# Connect_Interface.net
KiCad netlist of a schematic drawn in Altium Designer
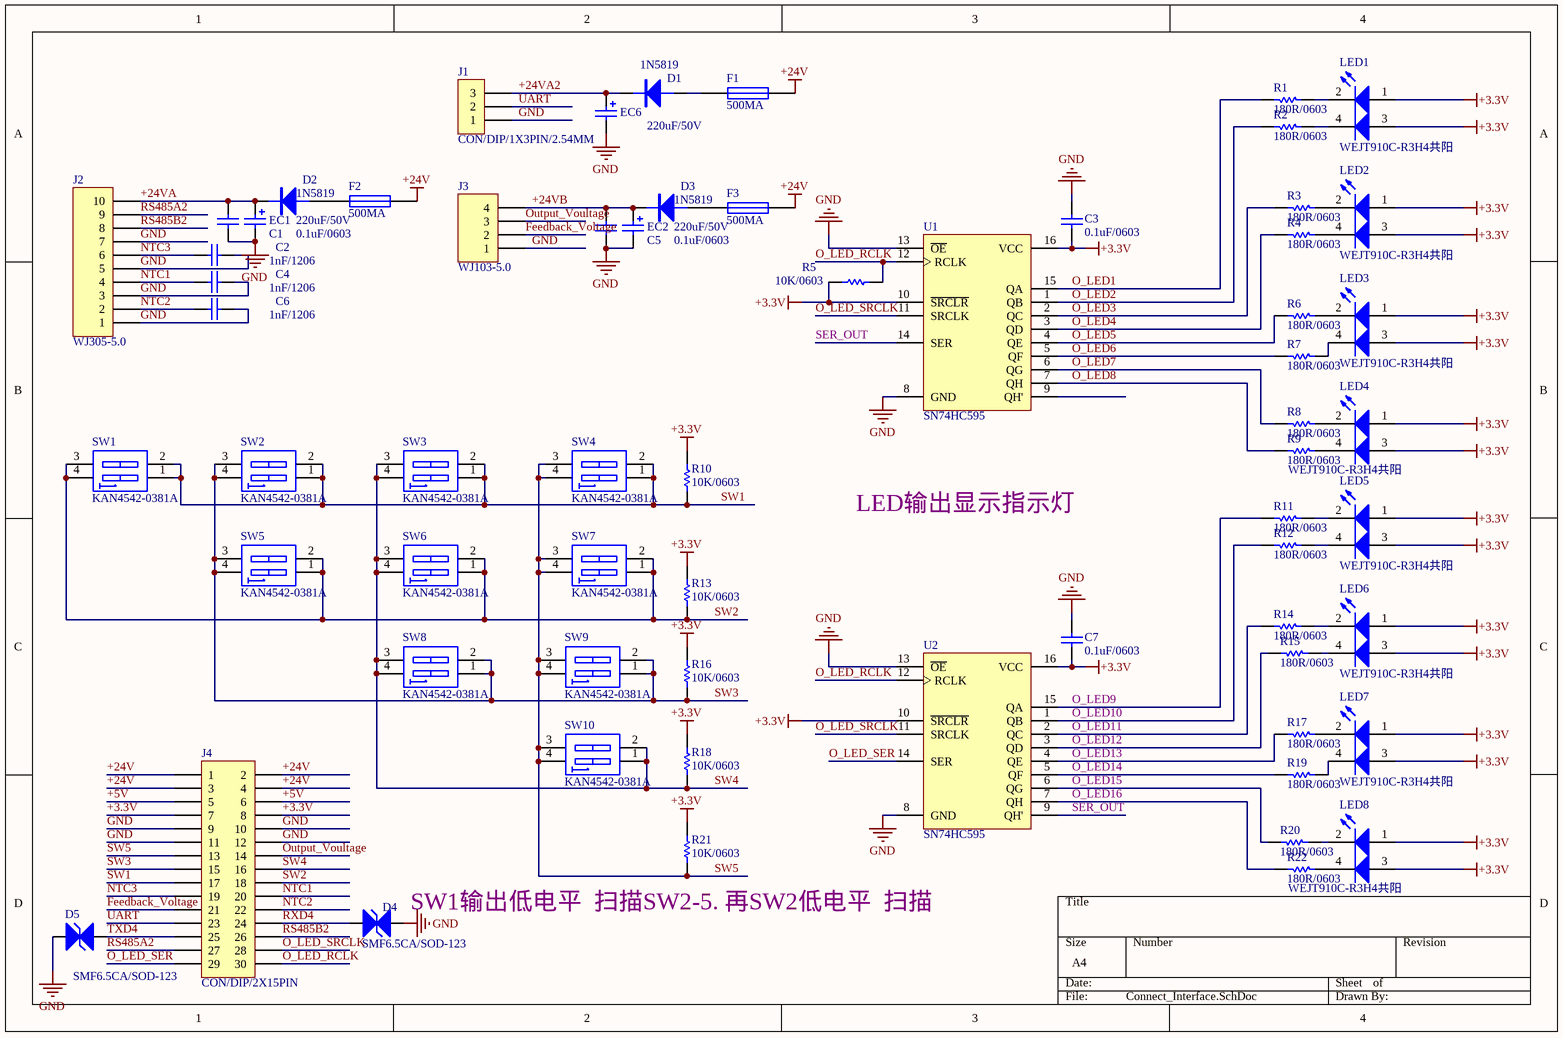
[diagram p0: Connect_Interface.SchDoc]

(export (version "E")
  (design (tool "Eeschema 10.0.6"))
  (components
    (comp (ref "C1")
      (value "0.1uF/0603")
      (footprint "CAP/SMT/0603C")
      (libsource (lib "Menred_原理图 封装库") (part "CAP/CAP/SMT/0603C"))
    )
    (comp (ref "C2")
      (value "1nF/1206")
      (footprint "CAP/SMT/1206C")
      (libsource (lib "") (part "CAP/CAP/SMT/0603C_1"))
    )
    (comp (ref "C3")
      (value "0.1uF/0603")
      (footprint "CAP/SMT/0603C")
      (libsource (lib "Menred_原理图 封装库") (part "CAP/CAP/SMT/0603C"))
    )
    (comp (ref "C4")
      (value "1nF/1206")
      (footprint "CAP/SMT/1206C")
      (libsource (lib "") (part "CAP/CAP/SMT/0603C_1"))
    )
    (comp (ref "C5")
      (value "0.1uF/0603")
      (footprint "CAP/SMT/0603C")
      (libsource (lib "Menred_原理图 封装库") (part "CAP/CAP/SMT/0603C"))
    )
    (comp (ref "C6")
      (value "1nF/1206")
      (footprint "CAP/SMT/1206C")
      (libsource (lib "") (part "CAP/CAP/SMT/0603C_1"))
    )
    (comp (ref "C7")
      (value "0.1uF/0603")
      (footprint "CAP/SMT/0603C")
      (libsource (lib "Menred_原理图 封装库") (part "CAP/CAP/SMT/0603C"))
    )
    (comp (ref "D1")
      (value "1N5819")
      (footprint "D/SMT/DO-214AC")
      (libsource (lib "Menred_原理图 封装库") (part "D/D/SMT/1N4007/DO-214"))
    )
    (comp (ref "D2")
      (value "1N5819")
      (footprint "D/SMT/DO-214AC")
      (libsource (lib "Menred_原理图 封装库") (part "D/D/SMT/1N5819/DO-214"))
    )
    (comp (ref "D3")
      (value "1N5819")
      (footprint "D/SMT/DO-214AC")
      (libsource (lib "Menred_原理图 封装库") (part "D/D/SMT/1N5819/DO-214"))
    )
    (comp (ref "D4")
      (value "SMF6.5CA/SOD-123")
      (footprint "D/SMT/SOD123")
      (libsource (lib "Menred_原理图 封装库") (part "D/TVS/SMT/SMF13CA/SOD-123"))
    )
    (comp (ref "D5")
      (value "SMF6.5CA/SOD-123")
      (footprint "D/SMT/SOD123")
      (libsource (lib "Menred_原理图 封装库") (part "D/TVS/SMT/SMF13CA/SOD-123"))
    )
    (comp (ref "EC1")
      (value "220uF/50V")
      (footprint "CAP/SMT/220UF/50V")
      (libsource (lib "Menred_原理图 封装库") (part "CAP/AEC/DIP/330uF/25V"))
    )
    (comp (ref "EC2")
      (value "220uF/50V")
      (footprint "CAP/SMT/220UF/50V")
      (libsource (lib "Menred_原理图 封装库") (part "CAP/AEC/DIP/330uF/25V"))
    )
    (comp (ref "EC6")
      (value "220uF/50V")
      (footprint "CAP/SMT/220UF/50V")
      (libsource (lib "Menred_原理图 封装库") (part "CAP/AEC/DIP/330uF/25V"))
    )
    (comp (ref "F1")
      (value "500MA")
      (footprint "FUSE/100MA/SMC")
      (libsource (lib "Menred_原理图 封装库") (part "FUSE/PTC/SMT/100MA"))
    )
    (comp (ref "F2")
      (value "500MA")
      (footprint "FUSE/100MA/SMC")
      (libsource (lib "Menred_原理图 封装库") (part "FUSE/PTC/SMT/100MA"))
    )
    (comp (ref "F3")
      (value "500MA")
      (footprint "FUSE/100MA/SMC")
      (libsource (lib "Menred_原理图 封装库") (part "FUSE/PTC/SMT/100MA"))
    )
    (comp (ref "J1")
      (value "CON/DIP/1X3PIN/2.54MM")
      (footprint "CON/DIP/1×3PIN/2.54MM/插件端子")
      (description "Connector")
      (libsource (lib "Menred_原理图 封装库") (part "CON/DIP/1X3PIN/2.54MM"))
    )
    (comp (ref "J2")
      (value "WJ305-5.0")
      (footprint "CON/DIP/1×10PIN/5.0MM/WJ103-10P")
      (description "Connector")
      (libsource (lib "Menred_原理图 封装库") (part "CON/DIP/1X10PIN/WJ305-5.0"))
    )
    (comp (ref "J3")
      (value "WJ103-5.0")
      (footprint "CON/DIP/1×4PIN/5.0MM/WJ103-4P")
      (description "Connector")
      (libsource (lib "Menred_原理图 封装库") (part "CON/DIP/1X4PIN/WJ103-5.0MM"))
    )
    (comp (ref "J4")
      (value "CON/DIP/2X15PIN")
      (footprint "CON/DIP/2X15PIN/2.54MM")
      (description "Connector")
      (fields (field (name "PUBLISHER") "Altium Limited"))
      (libsource (lib "Menred_原理图 封装库") (part "CON/DIP/2X15PIN"))
    )
    (comp (ref "LED1")
      (value "WEJT910C-R3H4共阳")
      (footprint "D/SMT/WEJT910C-R3H4")
      (libsource (lib "Menred_原理图 封装库") (part "D/LED/DIP/WEJT910C-R3H4-BA共阳"))
    )
    (comp (ref "LED2")
      (value "WEJT910C-R3H4共阳")
      (footprint "D/SMT/WEJT910C-R3H4")
      (libsource (lib "Menred_原理图 封装库") (part "D/LED/DIP/WEJT910C-R3H4-BA共阳"))
    )
    (comp (ref "LED3")
      (value "WEJT910C-R3H4共阳")
      (footprint "D/SMT/WEJT910C-R3H4")
      (libsource (lib "Menred_原理图 封装库") (part "D/LED/DIP/WEJT910C-R3H4-BA共阳"))
    )
    (comp (ref "LED4")
      (value "WEJT910C-R3H4共阳")
      (footprint "D/SMT/WEJT910C-R3H4")
      (libsource (lib "Menred_原理图 封装库") (part "D/LED/DIP/WEJT910C-R3H4-BA共阳"))
    )
    (comp (ref "LED5")
      (value "WEJT910C-R3H4共阳")
      (footprint "D/SMT/WEJT910C-R3H4")
      (libsource (lib "Menred_原理图 封装库") (part "D/LED/DIP/WEJT910C-R3H4-BA共阳"))
    )
    (comp (ref "LED6")
      (value "WEJT910C-R3H4共阳")
      (footprint "D/SMT/WEJT910C-R3H4")
      (libsource (lib "Menred_原理图 封装库") (part "D/LED/DIP/WEJT910C-R3H4-BA共阳"))
    )
    (comp (ref "LED7")
      (value "WEJT910C-R3H4共阳")
      (footprint "D/SMT/WEJT910C-R3H4")
      (libsource (lib "Menred_原理图 封装库") (part "D/LED/DIP/WEJT910C-R3H4-BA共阳"))
    )
    (comp (ref "LED8")
      (value "WEJT910C-R3H4共阳")
      (footprint "D/SMT/WEJT910C-R3H4")
      (libsource (lib "Menred_原理图 封装库") (part "D/LED/DIP/WEJT910C-R3H4-BA共阳"))
    )
    (comp (ref "R1")
      (value "180R/0603")
      (footprint "0603R")
      (libsource (lib "Menred_原理图 封装库") (part "RES/RES/SMT/0603"))
    )
    (comp (ref "R2")
      (value "180R/0603")
      (footprint "0603R")
      (libsource (lib "Menred_原理图 封装库") (part "RES/RES/SMT/0603"))
    )
    (comp (ref "R3")
      (value "180R/0603")
      (footprint "0603R")
      (libsource (lib "Menred_原理图 封装库") (part "RES/RES/SMT/0603"))
    )
    (comp (ref "R4")
      (value "180R/0603")
      (footprint "0603R")
      (libsource (lib "Menred_原理图 封装库") (part "RES/RES/SMT/0603"))
    )
    (comp (ref "R5")
      (value "10K/0603")
      (footprint "0603R")
      (libsource (lib "Menred_原理图 封装库") (part "RES/RES/SMT/0603"))
    )
    (comp (ref "R6")
      (value "180R/0603")
      (footprint "0603R")
      (libsource (lib "Menred_原理图 封装库") (part "RES/RES/SMT/0603"))
    )
    (comp (ref "R7")
      (value "180R/0603")
      (footprint "0603R")
      (libsource (lib "Menred_原理图 封装库") (part "RES/RES/SMT/0603"))
    )
    (comp (ref "R8")
      (value "180R/0603")
      (footprint "0603R")
      (libsource (lib "Menred_原理图 封装库") (part "RES/RES/SMT/0603"))
    )
    (comp (ref "R9")
      (value "180R/0603")
      (footprint "0603R")
      (libsource (lib "Menred_原理图 封装库") (part "RES/RES/SMT/0603"))
    )
    (comp (ref "R10")
      (value "10K/0603")
      (footprint "0603R")
      (libsource (lib "Menred_原理图 封装库") (part "RES/RES/SMT/0603"))
    )
    (comp (ref "R11")
      (value "180R/0603")
      (footprint "0603R")
      (libsource (lib "Menred_原理图 封装库") (part "RES/RES/SMT/0603"))
    )
    (comp (ref "R12")
      (value "180R/0603")
      (footprint "0603R")
      (libsource (lib "Menred_原理图 封装库") (part "RES/RES/SMT/0603"))
    )
    (comp (ref "R13")
      (value "10K/0603")
      (footprint "0603R")
      (libsource (lib "Menred_原理图 封装库") (part "RES/RES/SMT/0603"))
    )
    (comp (ref "R14")
      (value "180R/0603")
      (footprint "0603R")
      (libsource (lib "Menred_原理图 封装库") (part "RES/RES/SMT/0603"))
    )
    (comp (ref "R15")
      (value "180R/0603")
      (footprint "0603R")
      (libsource (lib "Menred_原理图 封装库") (part "RES/RES/SMT/0603"))
    )
    (comp (ref "R16")
      (value "10K/0603")
      (footprint "0603R")
      (libsource (lib "Menred_原理图 封装库") (part "RES/RES/SMT/0603"))
    )
    (comp (ref "R17")
      (value "180R/0603")
      (footprint "0603R")
      (libsource (lib "Menred_原理图 封装库") (part "RES/RES/SMT/0603"))
    )
    (comp (ref "R18")
      (value "10K/0603")
      (footprint "0603R")
      (libsource (lib "Menred_原理图 封装库") (part "RES/RES/SMT/0603"))
    )
    (comp (ref "R19")
      (value "180R/0603")
      (footprint "0603R")
      (libsource (lib "Menred_原理图 封装库") (part "RES/RES/SMT/0603"))
    )
    (comp (ref "R20")
      (value "180R/0603")
      (footprint "0603R")
      (libsource (lib "Menred_原理图 封装库") (part "RES/RES/SMT/0603"))
    )
    (comp (ref "R21")
      (value "10K/0603")
      (footprint "0603R")
      (libsource (lib "Menred_原理图 封装库") (part "RES/RES/SMT/0603"))
    )
    (comp (ref "R22")
      (value "180R/0603")
      (footprint "0603R")
      (libsource (lib "Menred_原理图 封装库") (part "RES/RES/SMT/0603"))
    )
    (comp (ref "SW1")
      (value "KAN4542-0381A")
      (footprint "SWITCH/KAN4542")
      (description "4.5mm*4.5mm*3.8mm")
      (libsource (lib "Menred_原理图 封装库") (part "SWITCH/TACT/SMT/KAN4542-0381A"))
    )
    (comp (ref "SW2")
      (value "KAN4542-0381A")
      (footprint "SWITCH/KAN4542")
      (description "4.5mm*4.5mm*3.8mm")
      (libsource (lib "Menred_原理图 封装库") (part "SWITCH/TACT/SMT/KAN4542-0381A"))
    )
    (comp (ref "SW3")
      (value "KAN4542-0381A")
      (footprint "SWITCH/KAN4542")
      (description "4.5mm*4.5mm*3.8mm")
      (libsource (lib "Menred_原理图 封装库") (part "SWITCH/TACT/SMT/KAN4542-0381A"))
    )
    (comp (ref "SW4")
      (value "KAN4542-0381A")
      (footprint "SWITCH/KAN4542")
      (description "4.5mm*4.5mm*3.8mm")
      (libsource (lib "Menred_原理图 封装库") (part "SWITCH/TACT/SMT/KAN4542-0381A"))
    )
    (comp (ref "SW5")
      (value "KAN4542-0381A")
      (footprint "SWITCH/KAN4542")
      (description "4.5mm*4.5mm*3.8mm")
      (libsource (lib "Menred_原理图 封装库") (part "SWITCH/TACT/SMT/KAN4542-0381A"))
    )
    (comp (ref "SW6")
      (value "KAN4542-0381A")
      (footprint "SWITCH/KAN4542")
      (description "4.5mm*4.5mm*3.8mm")
      (libsource (lib "Menred_原理图 封装库") (part "SWITCH/TACT/SMT/KAN4542-0381A"))
    )
    (comp (ref "SW7")
      (value "KAN4542-0381A")
      (footprint "SWITCH/KAN4542")
      (description "4.5mm*4.5mm*3.8mm")
      (libsource (lib "Menred_原理图 封装库") (part "SWITCH/TACT/SMT/KAN4542-0381A"))
    )
    (comp (ref "SW8")
      (value "KAN4542-0381A")
      (footprint "SWITCH/KAN4542")
      (description "4.5mm*4.5mm*3.8mm")
      (libsource (lib "Menred_原理图 封装库") (part "SWITCH/TACT/SMT/KAN4542-0381A"))
    )
    (comp (ref "SW9")
      (value "KAN4542-0381A")
      (footprint "SWITCH/KAN4542")
      (description "4.5mm*4.5mm*3.8mm")
      (libsource (lib "Menred_原理图 封装库") (part "SWITCH/TACT/SMT/KAN4542-0381A"))
    )
    (comp (ref "SW10")
      (value "KAN4542-0381A")
      (footprint "SWITCH/KAN4542")
      (description "4.5mm*4.5mm*3.8mm")
      (libsource (lib "Menred_原理图 封装库") (part "SWITCH/TACT/SMT/KAN4542-0381A"))
    )
    (comp (ref "U1")
      (value "SN74HC595")
      (footprint "SOP-16")
      (description "8-bit serial-in,serial or parallel-out shift register with output latches;3-state")
      (libsource (lib "Menred_原理图 封装库") (part "IC/TTL/SMT/SN74HC595"))
    )
    (comp (ref "U2")
      (value "SN74HC595")
      (footprint "SOP-16")
      (description "8-bit serial-in,serial or parallel-out shift register with output latches;3-state")
      (libsource (lib "Menred_原理图 封装库") (part "IC/TTL/SMT/SN74HC595"))
    )
  )
  (nets
    (net (code "1") (name "+3.3V") (class "Default")
      (node (ref "C3") (pin "1") (pinfunction "1_1") (pintype "passive"))
      (node (ref "C7") (pin "1") (pinfunction "1_1") (pintype "passive"))
      (node (ref "J4") (pin "7") (pinfunction "7_7") (pintype "passive"))
      (node (ref "J4") (pin "8") (pinfunction "8_8") (pintype "passive"))
      (node (ref "LED1") (pin "1") (pinfunction "A_1") (pintype "passive"))
      (node (ref "LED1") (pin "3") (pinfunction "A_3") (pintype "passive"))
      (node (ref "LED2") (pin "1") (pinfunction "A_1") (pintype "passive"))
      (node (ref "LED2") (pin "3") (pinfunction "A_3") (pintype "passive"))
      (node (ref "LED3") (pin "1") (pinfunction "A_1") (pintype "passive"))
      (node (ref "LED3") (pin "3") (pinfunction "A_3") (pintype "passive"))
      (node (ref "LED4") (pin "1") (pinfunction "A_1") (pintype "passive"))
      (node (ref "LED4") (pin "3") (pinfunction "A_3") (pintype "passive"))
      (node (ref "LED5") (pin "1") (pinfunction "A_1") (pintype "passive"))
      (node (ref "LED5") (pin "3") (pinfunction "A_3") (pintype "passive"))
      (node (ref "LED6") (pin "1") (pinfunction "A_1") (pintype "passive"))
      (node (ref "LED6") (pin "3") (pinfunction "A_3") (pintype "passive"))
      (node (ref "LED7") (pin "1") (pinfunction "A_1") (pintype "passive"))
      (node (ref "LED7") (pin "3") (pinfunction "A_3") (pintype "passive"))
      (node (ref "LED8") (pin "1") (pinfunction "A_1") (pintype "passive"))
      (node (ref "LED8") (pin "3") (pinfunction "A_3") (pintype "passive"))
      (node (ref "R10") (pin "2") (pinfunction "2_2") (pintype "passive"))
      (node (ref "R13") (pin "2") (pinfunction "2_2") (pintype "passive"))
      (node (ref "R16") (pin "2") (pinfunction "2_2") (pintype "passive"))
      (node (ref "R18") (pin "2") (pinfunction "2_2") (pintype "passive"))
      (node (ref "R21") (pin "2") (pinfunction "2_2") (pintype "passive"))
      (node (ref "R5") (pin "1") (pinfunction "1_1") (pintype "passive"))
      (node (ref "U1") (pin "10") (pinfunction "~{SRCLR}_10") (pintype "passive"))
      (node (ref "U1") (pin "16") (pinfunction "VCC_16") (pintype "passive"))
      (node (ref "U2") (pin "10") (pinfunction "~{SRCLR}_10") (pintype "passive"))
      (node (ref "U2") (pin "16") (pinfunction "VCC_16") (pintype "passive"))
    )
    (net (code "2") (name "+24V") (class "Default")
      (node (ref "F1") (pin "1") (pinfunction "1_1") (pintype "passive"))
      (node (ref "F2") (pin "2") (pinfunction "2_2") (pintype "passive"))
      (node (ref "F3") (pin "2") (pinfunction "2_2") (pintype "passive"))
      (node (ref "J4") (pin "1") (pinfunction "1_1") (pintype "passive"))
      (node (ref "J4") (pin "2") (pinfunction "2_2") (pintype "passive"))
      (node (ref "J4") (pin "3") (pinfunction "3_3") (pintype "passive"))
      (node (ref "J4") (pin "4") (pinfunction "4_4") (pintype "passive"))
    )
    (net (code "3") (name "/+5V") (class "Default")
      (node (ref "J4") (pin "5") (pinfunction "5_5") (pintype "passive"))
      (node (ref "J4") (pin "6") (pinfunction "6_6") (pintype "passive"))
    )
    (net (code "4") (name "/+24VA") (class "Default")
      (node (ref "C1") (pin "2") (pinfunction "2_2") (pintype "passive"))
      (node (ref "D2") (pin "1") (pinfunction "K_1") (pintype "passive"))
      (node (ref "EC1") (pin "1") (pinfunction "1_1") (pintype "passive"))
      (node (ref "J2") (pin "10") (pinfunction "10_10") (pintype "passive"))
    )
    (net (code "5") (name "/+24VA2") (class "Default")
      (node (ref "D1") (pin "1") (pinfunction "K_1") (pintype "passive"))
      (node (ref "EC6") (pin "1") (pinfunction "1_1") (pintype "passive"))
      (node (ref "J1") (pin "3") (pinfunction "3_3") (pintype "passive"))
    )
    (net (code "6") (name "/+24VB") (class "Default")
      (node (ref "C5") (pin "2") (pinfunction "2_2") (pintype "passive"))
      (node (ref "D3") (pin "1") (pinfunction "K_1") (pintype "passive"))
      (node (ref "EC2") (pin "1") (pinfunction "1_1") (pintype "passive"))
      (node (ref "J3") (pin "4") (pinfunction "4_4") (pintype "passive"))
    )
    (net (code "7") (name "/Feedback_Voltage") (class "Default")
      (node (ref "J3") (pin "2") (pinfunction "2_2") (pintype "passive"))
      (node (ref "J4") (pin "21") (pinfunction "21_21") (pintype "passive"))
    )
    (net (code "9") (name "/NTC1") (class "Default")
      (node (ref "C4") (pin "1") (pinfunction "1_1") (pintype "passive"))
      (node (ref "J2") (pin "4") (pinfunction "4_4") (pintype "passive"))
      (node (ref "J4") (pin "20") (pinfunction "20_20") (pintype "passive"))
    )
    (net (code "10") (name "/NTC2") (class "Default")
      (node (ref "C6") (pin "1") (pinfunction "1_1") (pintype "passive"))
      (node (ref "J2") (pin "2") (pinfunction "2_2") (pintype "passive"))
      (node (ref "J4") (pin "22") (pinfunction "22_22") (pintype "passive"))
    )
    (net (code "11") (name "/NTC3") (class "Default")
      (node (ref "C2") (pin "1") (pinfunction "1_1") (pintype "passive"))
      (node (ref "J2") (pin "6") (pinfunction "6_6") (pintype "passive"))
      (node (ref "J4") (pin "19") (pinfunction "19_19") (pintype "passive"))
    )
    (net (code "12") (name "/O_LED1") (class "Default")
      (node (ref "R1") (pin "1") (pinfunction "1_1") (pintype "passive"))
      (node (ref "U1") (pin "15") (pinfunction "QA_15") (pintype "passive"))
    )
    (net (code "13") (name "/O_LED2") (class "Default")
      (node (ref "R2") (pin "1") (pinfunction "1_1") (pintype "passive"))
      (node (ref "U1") (pin "1") (pinfunction "QB_1") (pintype "passive"))
    )
    (net (code "14") (name "/O_LED3") (class "Default")
      (node (ref "R3") (pin "1") (pinfunction "1_1") (pintype "passive"))
      (node (ref "U1") (pin "2") (pinfunction "QC_2") (pintype "passive"))
    )
    (net (code "15") (name "/O_LED4") (class "Default")
      (node (ref "R4") (pin "1") (pinfunction "1_1") (pintype "passive"))
      (node (ref "U1") (pin "3") (pinfunction "QD_3") (pintype "passive"))
    )
    (net (code "16") (name "/O_LED5") (class "Default")
      (node (ref "R6") (pin "1") (pinfunction "1_1") (pintype "passive"))
      (node (ref "U1") (pin "4") (pinfunction "QE_4") (pintype "passive"))
    )
    (net (code "17") (name "/O_LED6") (class "Default")
      (node (ref "R7") (pin "1") (pinfunction "1_1") (pintype "passive"))
      (node (ref "U1") (pin "5") (pinfunction "QF_5") (pintype "passive"))
    )
    (net (code "18") (name "/O_LED7") (class "Default")
      (node (ref "R8") (pin "1") (pinfunction "1_1") (pintype "passive"))
      (node (ref "U1") (pin "6") (pinfunction "QG_6") (pintype "passive"))
    )
    (net (code "19") (name "/O_LED8") (class "Default")
      (node (ref "R9") (pin "1") (pinfunction "1_1") (pintype "passive"))
      (node (ref "U1") (pin "7") (pinfunction "QH_7") (pintype "passive"))
    )
    (net (code "20") (name "/O_LED9") (class "Default")
      (node (ref "R11") (pin "1") (pinfunction "1_1") (pintype "passive"))
      (node (ref "U2") (pin "15") (pinfunction "QA_15") (pintype "passive"))
    )
    (net (code "21") (name "/O_LED10") (class "Default")
      (node (ref "R12") (pin "1") (pinfunction "1_1") (pintype "passive"))
      (node (ref "U2") (pin "1") (pinfunction "QB_1") (pintype "passive"))
    )
    (net (code "22") (name "/O_LED11") (class "Default")
      (node (ref "R14") (pin "1") (pinfunction "1_1") (pintype "passive"))
      (node (ref "U2") (pin "2") (pinfunction "QC_2") (pintype "passive"))
    )
    (net (code "23") (name "/O_LED12") (class "Default")
      (node (ref "R15") (pin "1") (pinfunction "1_1") (pintype "passive"))
      (node (ref "U2") (pin "3") (pinfunction "QD_3") (pintype "passive"))
    )
    (net (code "24") (name "/O_LED13") (class "Default")
      (node (ref "R17") (pin "1") (pinfunction "1_1") (pintype "passive"))
      (node (ref "U2") (pin "4") (pinfunction "QE_4") (pintype "passive"))
    )
    (net (code "25") (name "/O_LED14") (class "Default")
      (node (ref "R19") (pin "1") (pinfunction "1_1") (pintype "passive"))
      (node (ref "U2") (pin "5") (pinfunction "QF_5") (pintype "passive"))
    )
    (net (code "26") (name "/O_LED15") (class "Default")
      (node (ref "R20") (pin "1") (pinfunction "1_1") (pintype "passive"))
      (node (ref "U2") (pin "6") (pinfunction "QG_6") (pintype "passive"))
    )
    (net (code "27") (name "/O_LED16") (class "Default")
      (node (ref "R22") (pin "1") (pinfunction "1_1") (pintype "passive"))
      (node (ref "U2") (pin "7") (pinfunction "QH_7") (pintype "passive"))
    )
    (net (code "28") (name "/O_LED_RCLK") (class "Default")
      (node (ref "J4") (pin "30") (pinfunction "30_30") (pintype "passive"))
      (node (ref "R5") (pin "2") (pinfunction "2_2") (pintype "passive"))
      (node (ref "U1") (pin "12") (pinfunction "RCLK_12") (pintype "passive"))
      (node (ref "U2") (pin "12") (pinfunction "RCLK_12") (pintype "passive"))
    )
    (net (code "29") (name "/O_LED_SER") (class "Default")
      (node (ref "J4") (pin "29") (pinfunction "29_29") (pintype "passive"))
      (node (ref "U2") (pin "14") (pinfunction "SER_14") (pintype "passive"))
    )
    (net (code "30") (name "/O_LED_SRCLK") (class "Default")
      (node (ref "J4") (pin "28") (pinfunction "28_28") (pintype "passive"))
      (node (ref "U1") (pin "11") (pinfunction "SRCLK_11") (pintype "passive"))
      (node (ref "U2") (pin "11") (pinfunction "SRCLK_11") (pintype "passive"))
    )
    (net (code "31") (name "/Output_Voultage") (class "Default")
      (node (ref "J3") (pin "3") (pinfunction "3_3") (pintype "passive"))
      (node (ref "J4") (pin "14") (pinfunction "14_14") (pintype "passive"))
    )
    (net (code "32") (name "/RS485A2") (class "Default")
      (node (ref "J2") (pin "9") (pinfunction "9_9") (pintype "passive"))
      (node (ref "J4") (pin "27") (pinfunction "27_27") (pintype "passive"))
    )
    (net (code "33") (name "/RS485B2") (class "Default")
      (node (ref "J2") (pin "8") (pinfunction "8_8") (pintype "passive"))
      (node (ref "J4") (pin "26") (pinfunction "26_26") (pintype "passive"))
    )
    (net (code "34") (name "/RXD4") (class "Default")
      (node (ref "D4") (pin "1") (pinfunction "A_1") (pintype "passive"))
      (node (ref "J4") (pin "24") (pinfunction "24_24") (pintype "passive"))
    )
    (net (code "35") (name "/SER_OUT") (class "Default")
      (node (ref "U1") (pin "14") (pinfunction "SER_14") (pintype "passive"))
      (node (ref "U2") (pin "9") (pinfunction "QH'_9") (pintype "passive"))
    )
    (net (code "36") (name "/SW1") (class "Default")
      (node (ref "J4") (pin "17") (pinfunction "17_17") (pintype "passive"))
      (node (ref "R10") (pin "1") (pinfunction "1_1") (pintype "passive"))
      (node (ref "SW1") (pin "1") (pinfunction "A1_1") (pintype "passive"))
      (node (ref "SW1") (pin "2") (pinfunction "A2_2") (pintype "passive"))
      (node (ref "SW2") (pin "1") (pinfunction "A1_1") (pintype "passive"))
      (node (ref "SW2") (pin "2") (pinfunction "A2_2") (pintype "passive"))
      (node (ref "SW3") (pin "1") (pinfunction "A1_1") (pintype "passive"))
      (node (ref "SW3") (pin "2") (pinfunction "A2_2") (pintype "passive"))
      (node (ref "SW4") (pin "1") (pinfunction "A1_1") (pintype "passive"))
      (node (ref "SW4") (pin "2") (pinfunction "A2_2") (pintype "passive"))
    )
    (net (code "38") (name "/SW2") (class "Default")
      (node (ref "J4") (pin "18") (pinfunction "18_18") (pintype "passive"))
      (node (ref "R13") (pin "1") (pinfunction "1_1") (pintype "passive"))
      (node (ref "SW1") (pin "3") (pinfunction "B2_3") (pintype "passive"))
      (node (ref "SW1") (pin "4") (pinfunction "B1_4") (pintype "passive"))
      (node (ref "SW5") (pin "1") (pinfunction "A1_1") (pintype "passive"))
      (node (ref "SW5") (pin "2") (pinfunction "A2_2") (pintype "passive"))
      (node (ref "SW6") (pin "1") (pinfunction "A1_1") (pintype "passive"))
      (node (ref "SW6") (pin "2") (pinfunction "A2_2") (pintype "passive"))
      (node (ref "SW7") (pin "1") (pinfunction "A1_1") (pintype "passive"))
      (node (ref "SW7") (pin "2") (pinfunction "A2_2") (pintype "passive"))
    )
    (net (code "39") (name "/SW3") (class "Default")
      (node (ref "J4") (pin "15") (pinfunction "15_15") (pintype "passive"))
      (node (ref "R16") (pin "1") (pinfunction "1_1") (pintype "passive"))
      (node (ref "SW2") (pin "3") (pinfunction "B2_3") (pintype "passive"))
      (node (ref "SW2") (pin "4") (pinfunction "B1_4") (pintype "passive"))
      (node (ref "SW5") (pin "3") (pinfunction "B2_3") (pintype "passive"))
      (node (ref "SW5") (pin "4") (pinfunction "B1_4") (pintype "passive"))
      (node (ref "SW8") (pin "1") (pinfunction "A1_1") (pintype "passive"))
      (node (ref "SW8") (pin "2") (pinfunction "A2_2") (pintype "passive"))
      (node (ref "SW9") (pin "1") (pinfunction "A1_1") (pintype "passive"))
      (node (ref "SW9") (pin "2") (pinfunction "A2_2") (pintype "passive"))
    )
    (net (code "40") (name "/SW4") (class "Default")
      (node (ref "J4") (pin "16") (pinfunction "16_16") (pintype "passive"))
      (node (ref "R18") (pin "1") (pinfunction "1_1") (pintype "passive"))
      (node (ref "SW10") (pin "1") (pinfunction "A1_1") (pintype "passive"))
      (node (ref "SW10") (pin "2") (pinfunction "A2_2") (pintype "passive"))
      (node (ref "SW3") (pin "3") (pinfunction "B2_3") (pintype "passive"))
      (node (ref "SW3") (pin "4") (pinfunction "B1_4") (pintype "passive"))
      (node (ref "SW6") (pin "3") (pinfunction "B2_3") (pintype "passive"))
      (node (ref "SW6") (pin "4") (pinfunction "B1_4") (pintype "passive"))
      (node (ref "SW8") (pin "3") (pinfunction "B2_3") (pintype "passive"))
      (node (ref "SW8") (pin "4") (pinfunction "B1_4") (pintype "passive"))
    )
    (net (code "41") (name "/SW5") (class "Default")
      (node (ref "J4") (pin "13") (pinfunction "13_13") (pintype "passive"))
      (node (ref "R21") (pin "1") (pinfunction "1_1") (pintype "passive"))
      (node (ref "SW10") (pin "3") (pinfunction "B2_3") (pintype "passive"))
      (node (ref "SW10") (pin "4") (pinfunction "B1_4") (pintype "passive"))
      (node (ref "SW4") (pin "3") (pinfunction "B2_3") (pintype "passive"))
      (node (ref "SW4") (pin "4") (pinfunction "B1_4") (pintype "passive"))
      (node (ref "SW7") (pin "3") (pinfunction "B2_3") (pintype "passive"))
      (node (ref "SW7") (pin "4") (pinfunction "B1_4") (pintype "passive"))
      (node (ref "SW9") (pin "3") (pinfunction "B2_3") (pintype "passive"))
      (node (ref "SW9") (pin "4") (pinfunction "B1_4") (pintype "passive"))
    )
    (net (code "42") (name "/TXD4") (class "Default")
      (node (ref "D5") (pin "1") (pinfunction "A_1") (pintype "passive"))
      (node (ref "J4") (pin "25") (pinfunction "25_25") (pintype "passive"))
    )
    (net (code "43") (name "/UART") (class "Default")
      (node (ref "J1") (pin "2") (pinfunction "2_2") (pintype "passive"))
      (node (ref "J4") (pin "23") (pinfunction "23_23") (pintype "passive"))
    )
    (net (code "44") (name "GND") (class "Default")
      (node (ref "C1") (pin "1") (pinfunction "1_1") (pintype "passive"))
      (node (ref "C2") (pin "2") (pinfunction "2_2") (pintype "passive"))
      (node (ref "C3") (pin "2") (pinfunction "2_2") (pintype "passive"))
      (node (ref "C4") (pin "2") (pinfunction "2_2") (pintype "passive"))
      (node (ref "C5") (pin "1") (pinfunction "1_1") (pintype "passive"))
      (node (ref "C6") (pin "2") (pinfunction "2_2") (pintype "passive"))
      (node (ref "C7") (pin "2") (pinfunction "2_2") (pintype "passive"))
      (node (ref "D4") (pin "2") (pinfunction "K_2") (pintype "passive"))
      (node (ref "D5") (pin "2") (pinfunction "K_2") (pintype "passive"))
      (node (ref "EC1") (pin "2") (pinfunction "2_2") (pintype "passive"))
      (node (ref "EC2") (pin "2") (pinfunction "2_2") (pintype "passive"))
      (node (ref "EC6") (pin "2") (pinfunction "2_2") (pintype "passive"))
      (node (ref "J1") (pin "1") (pinfunction "1_1") (pintype "passive"))
      (node (ref "J2") (pin "1") (pinfunction "1_1") (pintype "passive"))
      (node (ref "J2") (pin "3") (pinfunction "3_3") (pintype "passive"))
      (node (ref "J2") (pin "5") (pinfunction "5_5") (pintype "passive"))
      (node (ref "J2") (pin "7") (pinfunction "7_7") (pintype "passive"))
      (node (ref "J3") (pin "1") (pinfunction "1_1") (pintype "passive"))
      (node (ref "J4") (pin "10") (pinfunction "10_10") (pintype "passive"))
      (node (ref "J4") (pin "11") (pinfunction "11_11") (pintype "passive"))
      (node (ref "J4") (pin "12") (pinfunction "12_12") (pintype "passive"))
      (node (ref "J4") (pin "9") (pinfunction "9_9") (pintype "passive"))
      (node (ref "U1") (pin "13") (pinfunction "~{OE}_13") (pintype "passive"))
      (node (ref "U1") (pin "8") (pinfunction "GND_8") (pintype "passive"))
      (node (ref "U2") (pin "13") (pinfunction "~{OE}_13") (pintype "passive"))
      (node (ref "U2") (pin "8") (pinfunction "GND_8") (pintype "passive"))
    )
    (net (code "45") (name "Net-(D1-A)") (class "Default")
      (node (ref "D1") (pin "2") (pinfunction "A_2") (pintype "passive"))
      (node (ref "F1") (pin "2") (pinfunction "2_2") (pintype "passive"))
    )
    (net (code "46") (name "Net-(D2-A)") (class "Default")
      (node (ref "D2") (pin "2") (pinfunction "A_2") (pintype "passive"))
      (node (ref "F2") (pin "1") (pinfunction "1_1") (pintype "passive"))
    )
    (net (code "47") (name "Net-(D3-A)") (class "Default")
      (node (ref "D3") (pin "2") (pinfunction "A_2") (pintype "passive"))
      (node (ref "F3") (pin "1") (pinfunction "1_1") (pintype "passive"))
    )
    (net (code "48") (name "Net-(LED1-K-Pad2)") (class "Default")
      (node (ref "LED1") (pin "2") (pinfunction "K_2") (pintype "passive"))
      (node (ref "R1") (pin "2") (pinfunction "2_2") (pintype "passive"))
    )
    (net (code "49") (name "Net-(LED1-K-Pad4)") (class "Default")
      (node (ref "LED1") (pin "4") (pinfunction "K_4") (pintype "passive"))
      (node (ref "R2") (pin "2") (pinfunction "2_2") (pintype "passive"))
    )
    (net (code "50") (name "Net-(LED2-K-Pad2)") (class "Default")
      (node (ref "LED2") (pin "2") (pinfunction "K_2") (pintype "passive"))
      (node (ref "R3") (pin "2") (pinfunction "2_2") (pintype "passive"))
    )
    (net (code "51") (name "Net-(LED2-K-Pad4)") (class "Default")
      (node (ref "LED2") (pin "4") (pinfunction "K_4") (pintype "passive"))
      (node (ref "R4") (pin "2") (pinfunction "2_2") (pintype "passive"))
    )
    (net (code "52") (name "Net-(LED3-K-Pad2)") (class "Default")
      (node (ref "LED3") (pin "2") (pinfunction "K_2") (pintype "passive"))
      (node (ref "R6") (pin "2") (pinfunction "2_2") (pintype "passive"))
    )
    (net (code "53") (name "Net-(LED3-K-Pad4)") (class "Default")
      (node (ref "LED3") (pin "4") (pinfunction "K_4") (pintype "passive"))
      (node (ref "R7") (pin "2") (pinfunction "2_2") (pintype "passive"))
    )
    (net (code "54") (name "Net-(LED4-K-Pad2)") (class "Default")
      (node (ref "LED4") (pin "2") (pinfunction "K_2") (pintype "passive"))
      (node (ref "R8") (pin "2") (pinfunction "2_2") (pintype "passive"))
    )
    (net (code "55") (name "Net-(LED4-K-Pad4)") (class "Default")
      (node (ref "LED4") (pin "4") (pinfunction "K_4") (pintype "passive"))
      (node (ref "R9") (pin "2") (pinfunction "2_2") (pintype "passive"))
    )
    (net (code "56") (name "Net-(LED5-K-Pad2)") (class "Default")
      (node (ref "LED5") (pin "2") (pinfunction "K_2") (pintype "passive"))
      (node (ref "R11") (pin "2") (pinfunction "2_2") (pintype "passive"))
    )
    (net (code "57") (name "Net-(LED5-K-Pad4)") (class "Default")
      (node (ref "LED5") (pin "4") (pinfunction "K_4") (pintype "passive"))
      (node (ref "R12") (pin "2") (pinfunction "2_2") (pintype "passive"))
    )
    (net (code "58") (name "Net-(LED6-K-Pad2)") (class "Default")
      (node (ref "LED6") (pin "2") (pinfunction "K_2") (pintype "passive"))
      (node (ref "R14") (pin "2") (pinfunction "2_2") (pintype "passive"))
    )
    (net (code "59") (name "Net-(LED6-K-Pad4)") (class "Default")
      (node (ref "LED6") (pin "4") (pinfunction "K_4") (pintype "passive"))
      (node (ref "R15") (pin "2") (pinfunction "2_2") (pintype "passive"))
    )
    (net (code "60") (name "Net-(LED7-K-Pad2)") (class "Default")
      (node (ref "LED7") (pin "2") (pinfunction "K_2") (pintype "passive"))
      (node (ref "R17") (pin "2") (pinfunction "2_2") (pintype "passive"))
    )
    (net (code "61") (name "Net-(LED7-K-Pad4)") (class "Default")
      (node (ref "LED7") (pin "4") (pinfunction "K_4") (pintype "passive"))
      (node (ref "R19") (pin "2") (pinfunction "2_2") (pintype "passive"))
    )
    (net (code "62") (name "Net-(LED8-K-Pad2)") (class "Default")
      (node (ref "LED8") (pin "2") (pinfunction "K_2") (pintype "passive"))
      (node (ref "R20") (pin "2") (pinfunction "2_2") (pintype "passive"))
    )
    (net (code "63") (name "Net-(LED8-K-Pad4)") (class "Default")
      (node (ref "LED8") (pin "4") (pinfunction "K_4") (pintype "passive"))
      (node (ref "R22") (pin "2") (pinfunction "2_2") (pintype "passive"))
    )
    (net (code "64") (name "unconnected-(U1-QH'-Pad9)") (class "Default")
      (node (ref "U1") (pin "9") (pinfunction "QH'_9") (pintype "passive"))
    )
  )
)
